# S04-SPEAKER.net
KiCad netlist of a schematic drawn in Altium Designer
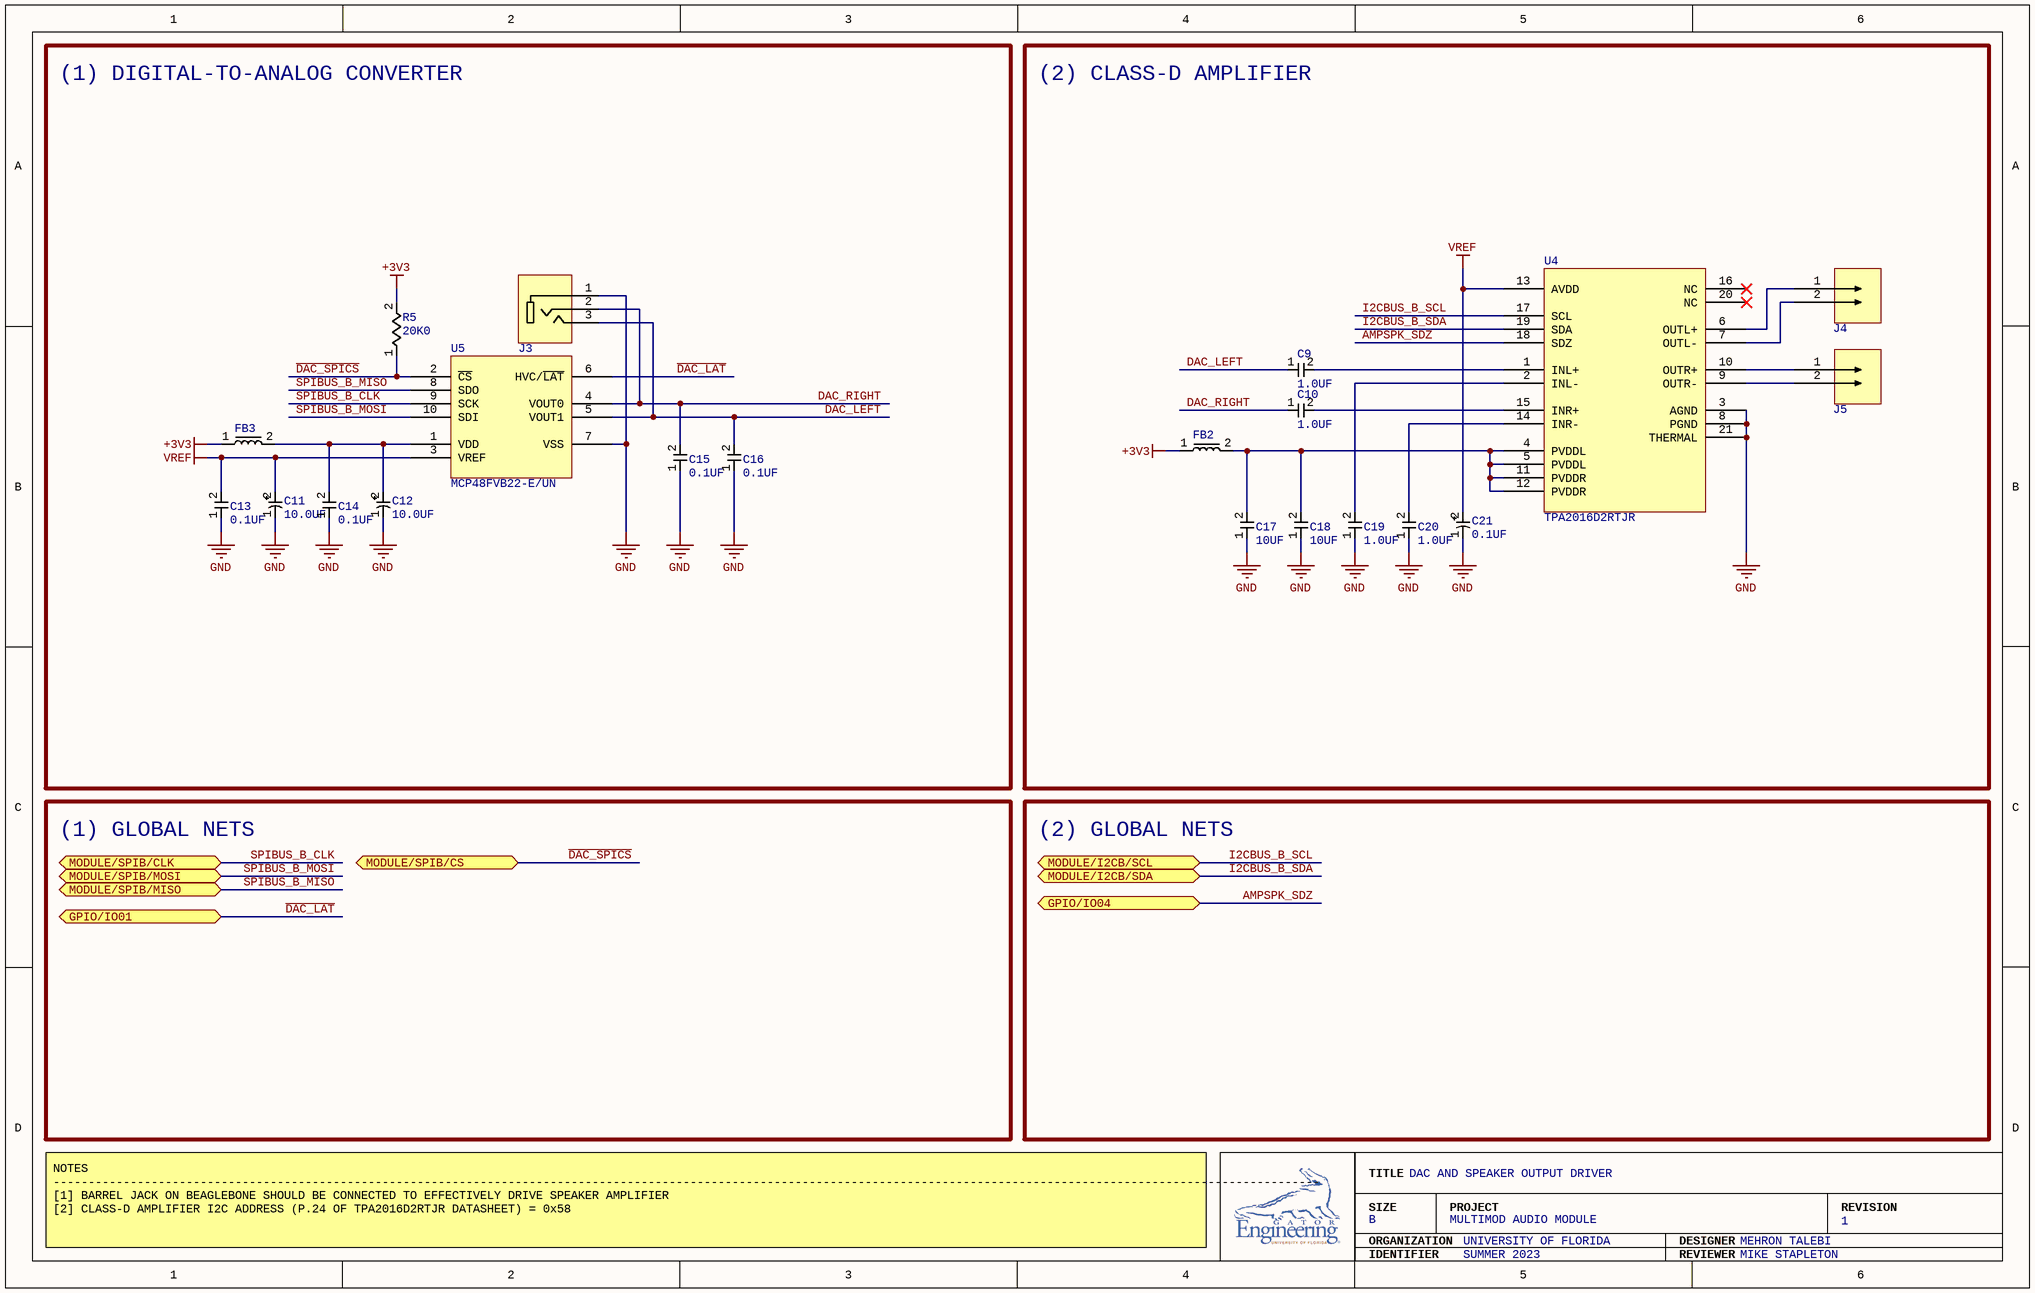
[diagram p0: S04-SPEAKER.SchDoc]

(export (version "E")
  (design (tool "Eeschema 10.0.6"))
  (components
    (comp (ref "C9")
      (value "1.0UF")
      (footprint "CL21B105KAFNFNE")
      (description "CAP CER 1UF 25V X7R 0805")
      (fields (field (name "TOLERANCE") "±10%"))
      (libsource (lib "Master") (part "CL21B105KAFNFNE"))
    )
    (comp (ref "C10")
      (value "1.0UF")
      (footprint "CL21B105KAFNFNE")
      (description "CAP CER 1UF 25V X7R 0805")
      (fields (field (name "TOLERANCE") "±10%"))
      (libsource (lib "Master") (part "CL21B105KAFNFNE"))
    )
    (comp (ref "C11")
      (value "10.0UF")
      (footprint "TAJR106M006RNJ")
      (description "CAP TANT 10UF 20% 6.3V 0805")
      (fields (field (name "TOLERANCE") "±20%"))
      (libsource (lib "Master") (part "TAJR106M006RNJ"))
    )
    (comp (ref "C12")
      (value "10.0UF")
      (footprint "TAJR106M006RNJ")
      (description "CAP TANT 10UF 20% 6.3V 0805")
      (fields (field (name "TOLERANCE") "±20%"))
      (libsource (lib "Master") (part "TAJR106M006RNJ"))
    )
    (comp (ref "C13")
      (value "0.1UF")
      (footprint "CL21B104KACNNNC")
      (description "CAP CER 0.1UF 25V X7R 0805")
      (fields (field (name "TOLERANCE") "±10%"))
      (libsource (lib "Master") (part "CL21B104KACNNNC"))
    )
    (comp (ref "C14")
      (value "0.1UF")
      (footprint "CL21B104KACNNNC")
      (description "CAP CER 0.1UF 25V X7R 0805")
      (fields (field (name "TOLERANCE") "±10%"))
      (libsource (lib "Master") (part "CL21B104KACNNNC"))
    )
    (comp (ref "C15")
      (value "0.1UF")
      (footprint "CL21B104KACNNNC")
      (description "CAP CER 0.1UF 25V X7R 0805")
      (fields (field (name "TOLERANCE") "±10%"))
      (libsource (lib "Master") (part "CL21B104KACNNNC"))
    )
    (comp (ref "C16")
      (value "0.1UF")
      (footprint "CL21B104KACNNNC")
      (description "CAP CER 0.1UF 25V X7R 0805")
      (fields (field (name "TOLERANCE") "±10%"))
      (libsource (lib "Master") (part "CL21B104KACNNNC"))
    )
    (comp (ref "C17")
      (value "10UF")
      (footprint "CL21B106KPQNFNE")
      (description "CAP CER 10UF 10V X7R 0805")
      (fields (field (name "TOLERANCE") "±10%"))
      (libsource (lib "Master") (part "CL21B106KPQNFNE"))
    )
    (comp (ref "C18")
      (value "10UF")
      (footprint "CL21B106KPQNFNE")
      (description "CAP CER 10UF 10V X7R 0805")
      (fields (field (name "TOLERANCE") "±10%"))
      (libsource (lib "Master") (part "CL21B106KPQNFNE"))
    )
    (comp (ref "C19")
      (value "1.0UF")
      (footprint "CL21B105KAFNFNE")
      (description "CAP CER 1UF 25V X7R 0805")
      (fields (field (name "TOLERANCE") "±10%"))
      (libsource (lib "Master") (part "CL21B105KAFNFNE"))
    )
    (comp (ref "C20")
      (value "1.0UF")
      (footprint "CL21B105KAFNFNE")
      (description "CAP CER 1UF 25V X7R 0805")
      (fields (field (name "TOLERANCE") "±10%"))
      (libsource (lib "Master") (part "CL21B105KAFNFNE"))
    )
    (comp (ref "C21")
      (value "0.1UF")
      (footprint "TAJR104K035RNJ")
      (description "CAP TANT 0.1UF 10% 35V 0805")
      (fields (field (name "TOLERANCE") "±10%"))
      (libsource (lib "Master") (part "TAJR104K035RNJ"))
    )
    (comp (ref "FB2")
      (value "BLM21PG221SN1D")
      (footprint "BLM21PG221SN1D")
      (description "FERRITE BEAD 220 OHM 0805 1LN")
      (libsource (lib "Master") (part "BLM21PG221SN1D"))
    )
    (comp (ref "FB3")
      (value "ILBB0805ER102V")
      (footprint "ILBB0805ER102V")
      (description "FERRITE BEAD 1K OHM 0805 1LN")
      (libsource (lib "Master") (part "ILBB0805ER102V"))
    )
    (comp (ref "J3")
      (value "SJ-3523-SMT-TR")
      (footprint "SJ-3523-SMT-TR")
      (description "CONN JACK STEREO 3.5MM SMD R/A")
      (libsource (lib "Master") (part "SJ-3523-SMT-TR"))
    )
    (comp (ref "J4")
      (value "TB001-500-02BE")
      (footprint "TB001-500-02BE")
      (description "TERMINAL BLOCK, SCREW TYPE, 5.00")
      (fields (field (name "VOLTAGE") "300 V"))
      (libsource (lib "Master") (part "TB001-500-02BE"))
    )
    (comp (ref "J5")
      (value "TB001-500-02BE")
      (footprint "TB001-500-02BE")
      (description "TERMINAL BLOCK, SCREW TYPE, 5.00")
      (fields (field (name "VOLTAGE") "300 V"))
      (libsource (lib "Master") (part "TB001-500-02BE"))
    )
    (comp (ref "R5")
      (value "20K0")
      (footprint "RC0805FR-074K7L")
      (description "RES 20K OHM 1% 1/8W 0805")
      (fields (field (name "TOLERANCE") "±1%"))
      (libsource (lib "Master") (part "RC0805FR-0720KL"))
    )
    (comp (ref "U4")
      (value "TPA2016D2RTJR")
      (footprint "TPA2016D2RTJR")
      (description "IC AMP CLASS D STEREO 2.8W 20QFN")
      (libsource (lib "Master") (part "TPA2016D2RTJR"))
    )
    (comp (ref "U5")
      (value "MCP48FVB22-E/UN")
      (footprint "MCP48FVB22-E/UN")
      (description "IC DAC 12BIT V-OUT 10MSOP")
      (libsource (lib "Master") (part "MCP48FVB22-E/UN"))
    )
  )
  (nets
    (net (code "1") (name "+3V3") (class "Default")
      (node (ref "FB2") (pin "1") (pinfunction "1_1") (pintype "passive"))
      (node (ref "FB3") (pin "1") (pinfunction "1_1") (pintype "passive"))
      (node (ref "R5") (pin "2") (pinfunction "2_2") (pintype "passive"))
    )
    (net (code "2") (name "/AMPSPK_SDZ") (class "Default")
      (node (ref "U4") (pin "18") (pinfunction "SDZ_18") (pintype "passive"))
    )
    (net (code "3") (name "/DAC_LAT") (class "Default")
      (node (ref "U5") (pin "6") (pinfunction "HVC/~{LAT}_6") (pintype "passive"))
    )
    (net (code "4") (name "/DAC_LEFT") (class "Default")
      (node (ref "C16") (pin "2") (pinfunction "2_2") (pintype "passive"))
      (node (ref "C9") (pin "1") (pinfunction "1_1") (pintype "passive"))
      (node (ref "J3") (pin "3") (pinfunction "3_3") (pintype "passive"))
      (node (ref "U5") (pin "5") (pinfunction "VOUT1_5") (pintype "passive"))
    )
    (net (code "5") (name "/DAC_RIGHT") (class "Default")
      (node (ref "C10") (pin "1") (pinfunction "1_1") (pintype "passive"))
      (node (ref "C15") (pin "2") (pinfunction "2_2") (pintype "passive"))
      (node (ref "J3") (pin "2") (pinfunction "2_2") (pintype "passive"))
      (node (ref "U5") (pin "4") (pinfunction "VOUT0_4") (pintype "passive"))
    )
    (net (code "6") (name "/DAC_SPICS") (class "Default")
      (node (ref "R5") (pin "1") (pinfunction "1_1") (pintype "passive"))
      (node (ref "U5") (pin "2") (pinfunction "CS_2") (pintype "passive"))
    )
    (net (code "7") (name "/I2CBUS_B_SCL") (class "Default")
      (node (ref "U4") (pin "17") (pinfunction "SCL_17") (pintype "passive"))
    )
    (net (code "8") (name "/I2CBUS_B_SDA") (class "Default")
      (node (ref "U4") (pin "19") (pinfunction "SDA_19") (pintype "passive"))
    )
    (net (code "9") (name "/SPIBUS_B_CLK") (class "Default")
      (node (ref "U5") (pin "9") (pinfunction "SCK_9") (pintype "passive"))
    )
    (net (code "10") (name "/SPIBUS_B_MISO") (class "Default")
      (node (ref "U5") (pin "8") (pinfunction "SDO_8") (pintype "passive"))
    )
    (net (code "11") (name "/SPIBUS_B_MOSI") (class "Default")
      (node (ref "U5") (pin "10") (pinfunction "SDI_10") (pintype "passive"))
    )
    (net (code "12") (name "GND") (class "Default")
      (node (ref "C11") (pin "1") (pinfunction "1_1") (pintype "passive"))
      (node (ref "C12") (pin "1") (pinfunction "1_1") (pintype "passive"))
      (node (ref "C13") (pin "1") (pinfunction "1_1") (pintype "passive"))
      (node (ref "C14") (pin "1") (pinfunction "1_1") (pintype "passive"))
      (node (ref "C15") (pin "1") (pinfunction "1_1") (pintype "passive"))
      (node (ref "C16") (pin "1") (pinfunction "1_1") (pintype "passive"))
      (node (ref "C17") (pin "1") (pinfunction "1_1") (pintype "passive"))
      (node (ref "C18") (pin "1") (pinfunction "1_1") (pintype "passive"))
      (node (ref "C19") (pin "1") (pinfunction "1_1") (pintype "passive"))
      (node (ref "C20") (pin "1") (pinfunction "1_1") (pintype "passive"))
      (node (ref "C21") (pin "1") (pinfunction "1_1") (pintype "passive"))
      (node (ref "J3") (pin "1") (pinfunction "1_1") (pintype "passive"))
      (node (ref "U4") (pin "21") (pinfunction "THERMAL_21") (pintype "passive"))
      (node (ref "U4") (pin "3") (pinfunction "AGND_3") (pintype "passive"))
      (node (ref "U4") (pin "8") (pinfunction "PGND_8") (pintype "passive"))
      (node (ref "U5") (pin "7") (pinfunction "VSS_7") (pintype "passive"))
    )
    (net (code "13") (name "Net-(C17-Pad2)") (class "Default")
      (node (ref "C17") (pin "2") (pinfunction "2_2") (pintype "passive"))
      (node (ref "C18") (pin "2") (pinfunction "2_2") (pintype "passive"))
      (node (ref "FB2") (pin "2") (pinfunction "2_2") (pintype "passive"))
      (node (ref "U4") (pin "11") (pinfunction "PVDDR_11") (pintype "passive"))
      (node (ref "U4") (pin "12") (pinfunction "PVDDR_12") (pintype "passive"))
      (node (ref "U4") (pin "4") (pinfunction "PVDDL_4") (pintype "passive"))
      (node (ref "U4") (pin "5") (pinfunction "PVDDL_5") (pintype "passive"))
    )
    (net (code "14") (name "Net-(U4-INL+)") (class "Default")
      (node (ref "C9") (pin "2") (pinfunction "2_2") (pintype "passive"))
      (node (ref "U4") (pin "1") (pinfunction "INL+_1") (pintype "passive"))
    )
    (net (code "15") (name "Net-(U4-INL-)") (class "Default")
      (node (ref "C19") (pin "2") (pinfunction "2_2") (pintype "passive"))
      (node (ref "U4") (pin "2") (pinfunction "INL-_2") (pintype "passive"))
    )
    (net (code "16") (name "Net-(U4-INR+)") (class "Default")
      (node (ref "C10") (pin "2") (pinfunction "2_2") (pintype "passive"))
      (node (ref "U4") (pin "15") (pinfunction "INR+_15") (pintype "passive"))
    )
    (net (code "17") (name "Net-(U4-INR-)") (class "Default")
      (node (ref "C20") (pin "2") (pinfunction "2_2") (pintype "passive"))
      (node (ref "U4") (pin "14") (pinfunction "INR-_14") (pintype "passive"))
    )
    (net (code "18") (name "Net-(U4-OUTL+)") (class "Default")
      (node (ref "J4") (pin "1") (pinfunction "1_1") (pintype "passive"))
      (node (ref "U4") (pin "6") (pinfunction "OUTL+_6") (pintype "passive"))
    )
    (net (code "19") (name "Net-(U4-OUTL-)") (class "Default")
      (node (ref "J4") (pin "2") (pinfunction "2_2") (pintype "passive"))
      (node (ref "U4") (pin "7") (pinfunction "OUTL-_7") (pintype "passive"))
    )
    (net (code "20") (name "Net-(U4-OUTR+)") (class "Default")
      (node (ref "J5") (pin "1") (pinfunction "1_1") (pintype "passive"))
      (node (ref "U4") (pin "10") (pinfunction "OUTR+_10") (pintype "passive"))
    )
    (net (code "21") (name "Net-(U4-OUTR-)") (class "Default")
      (node (ref "J5") (pin "2") (pinfunction "2_2") (pintype "passive"))
      (node (ref "U4") (pin "9") (pinfunction "OUTR-_9") (pintype "passive"))
    )
    (net (code "22") (name "Net-(U5-VDD)") (class "Default")
      (node (ref "C12") (pin "2") (pinfunction "2_2") (pintype "passive"))
      (node (ref "C14") (pin "2") (pinfunction "2_2") (pintype "passive"))
      (node (ref "FB3") (pin "2") (pinfunction "2_2") (pintype "passive"))
      (node (ref "U5") (pin "1") (pinfunction "VDD_1") (pintype "passive"))
    )
    (net (code "23") (name "VREF") (class "Default")
      (node (ref "C11") (pin "2") (pinfunction "2_2") (pintype "passive"))
      (node (ref "C13") (pin "2") (pinfunction "2_2") (pintype "passive"))
      (node (ref "C21") (pin "2") (pinfunction "2_2") (pintype "passive"))
      (node (ref "U4") (pin "13") (pinfunction "AVDD_13") (pintype "passive"))
      (node (ref "U5") (pin "3") (pinfunction "VREF_3") (pintype "passive"))
    )
    (net (code "24") (name "unconnected-(U4-NC-Pad16)") (class "Default")
      (node (ref "U4") (pin "16") (pinfunction "NC_16") (pintype "passive+no_connect"))
    )
    (net (code "25") (name "unconnected-(U4-NC-Pad20)") (class "Default")
      (node (ref "U4") (pin "20") (pinfunction "NC_20") (pintype "passive+no_connect"))
    )
  )
)
